# USB_OTG_FS.net
KiCad netlist of a schematic drawn in Altium Designer
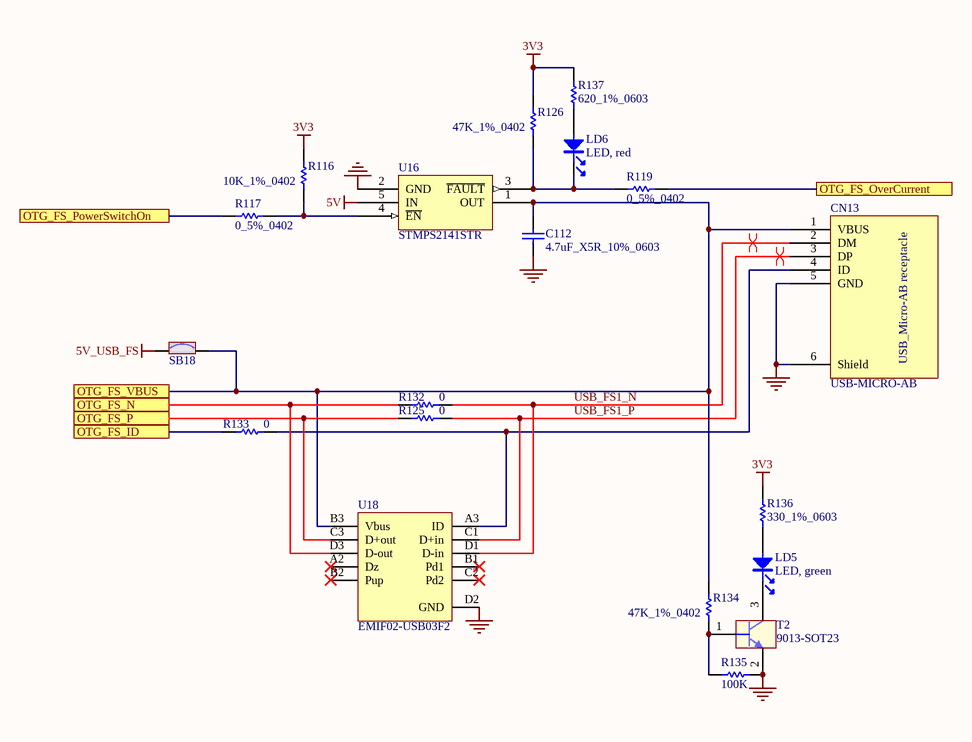
[diagram p0: USB_OTG_FS.SchDoc]

(export (version "E")
  (design (tool "Eeschema 10.0.6"))
  (components
    (comp (ref "C112")
      (value "4.7uF_X5R_10%_0603")
      (footprint "0603C")
      (description "Capacitor,4.7uF,16V, X5R,10%,0603,YAGEO")
      (libsource (lib "MCD_TOOLS") (part "Cap_4.7uF_X5R_10%_0603"))
    )
    (comp (ref "CN13")
      (value "USB-MICRO-AB")
      (footprint "USB-MICRO-AB")
      (description "USB-MICRO-AB, 47590-0001, SMT, MOLEX")
      (libsource (lib "MCD_TOOLS") (part "USB-MICRO-AB"))
    )
    (comp (ref "LD5")
      (value "LED, green")
      (footprint "0603D")
      (description "LED, green, 0603")
      (libsource (lib "MCD_TOOLS") (part "LED_green"))
    )
    (comp (ref "LD6")
      (value "LED, red")
      (footprint "0603D")
      (description "LED, red, 0603")
      (libsource (lib "MCD_TOOLS") (part "LED_red"))
    )
    (comp (ref "R116")
      (value "10K_1%_0402")
      (footprint "0402R")
      (description "Resistor,10K,0402,1%,YAGEO")
      (libsource (lib "MCD_TOOLS") (part "Res_10K_1%_0402"))
    )
    (comp (ref "R117")
      (value "0_5%_0402")
      (footprint "0402R")
      (description "Resistor,0,0402,5%,YAGEO")
      (libsource (lib "MCD_TOOLS") (part "Res_0_5%_0402"))
    )
    (comp (ref "R119")
      (value "0_5%_0402")
      (footprint "0402R")
      (description "Resistor,0,0402,5%,YAGEO")
      (libsource (lib "MCD_TOOLS") (part "Res_0_5%_0402"))
    )
    (comp (ref "R125")
      (value "0")
      (footprint "0402R")
      (description "Resistor,0,0402,5%,YAGEO")
      (libsource (lib "MCD_TOOLS") (part "Res_0_5%_0402"))
    )
    (comp (ref "R126")
      (value "47K_1%_0402")
      (footprint "0402R")
      (description "Resistor,47K,0402,1%,YAGEO")
      (libsource (lib "MCD_TOOLS") (part "Res_47K_1%_0402"))
    )
    (comp (ref "R132")
      (value "0")
      (footprint "0402R")
      (description "Resistor,0,0402,5%,YAGEO")
      (libsource (lib "MCD_TOOLS") (part "Res_0_5%_0402"))
    )
    (comp (ref "R133")
      (value "0")
      (footprint "0402R")
      (description "Resistor,0,0402,5%,YAGEO")
      (libsource (lib "MCD_TOOLS") (part "Res_0_5%_0402"))
    )
    (comp (ref "R134")
      (value "47K_1%_0402")
      (footprint "0402R")
      (description "Resistor,47K,0402,1%,YAGEO")
      (libsource (lib "MCD_TOOLS") (part "Res_47K_1%_0402"))
    )
    (comp (ref "R135")
      (value "100K")
      (footprint "0402R")
      (description "Resistor,100K,0402,1%,YAGEO")
      (libsource (lib "MCD_TOOLS") (part "Res_100K_1%_0402"))
    )
    (comp (ref "R136")
      (value "330_1%_0603")
      (footprint "0603R")
      (description "Resistor,330,0603,1%,YAGEO")
      (libsource (lib "MCD_TOOLS") (part "Res_330_1%_0603"))
    )
    (comp (ref "R137")
      (value "620_1%_0603")
      (footprint "0603R")
      (description "Resistor,620,0603,1%,VISHAY")
      (libsource (lib "MCD_TOOLS") (part "Res_620_1%_0603"))
    )
    (comp (ref "SB18")
      (value "Solder Bridge ON")
      (footprint "JP2_SMD")
      (libsource (lib "MCD_TOOLS") (part "SB_ON"))
    )
    (comp (ref "T2")
      (value "9013-SOT23")
      (footprint "SOT23")
      (description "NPN Bipolar Transistor")
      (libsource (lib "MCD_TOOLS") (part "9013-SOT23"))
    )
    (comp (ref "U16")
      (value "STMPS2141STR")
      (footprint "SOT23-5L")
      (description "Enhanced single channel power switches")
      (libsource (lib "MCD_TOOLS") (part "STMPS2141STR"))
    )
    (comp (ref "U18")
      (value "EMIF02-USB03F2")
      (footprint "Flip Chip")
      (description "2-line IPAD, EMI filter including ESD protection")
      (libsource (lib "MCD_TOOLS") (part "EMIF02-USB03F2"))
    )
  )
  (nets
    (net (code "1") (name "/OTG_FS_ID") (class "Default")
      (node (ref "R133") (pin "1") (pinfunction "1_1") (pintype "passive"))
    )
    (net (code "2") (name "/OTG_FS_N") (class "Default")
      (node (ref "R132") (pin "1") (pinfunction "1_1") (pintype "passive"))
      (node (ref "U18") (pin "D3") (pinfunction "D-out_D3") (pintype "passive"))
    )
    (net (code "3") (name "/OTG_FS_OverCurrent") (class "Default")
      (node (ref "R119") (pin "2") (pinfunction "2_2") (pintype "passive"))
    )
    (net (code "4") (name "/OTG_FS_P") (class "Default")
      (node (ref "R125") (pin "1") (pinfunction "1_1") (pintype "passive"))
      (node (ref "U18") (pin "C3") (pinfunction "D+out_C3") (pintype "passive"))
    )
    (net (code "5") (name "/OTG_FS_PowerSwitchOn") (class "Default")
      (node (ref "R117") (pin "1") (pinfunction "1_1") (pintype "passive"))
    )
    (net (code "6") (name "/OTG_FS_VBUS") (class "Default")
      (node (ref "C112") (pin "2") (pinfunction "2_2") (pintype "passive"))
      (node (ref "CN13") (pin "1") (pinfunction "VBUS_1") (pintype "passive"))
      (node (ref "R134") (pin "2") (pinfunction "2_2") (pintype "passive"))
      (node (ref "SB18") (pin "2") (pinfunction "2_2") (pintype "passive"))
      (node (ref "U16") (pin "1") (pinfunction "OUT_1") (pintype "passive"))
      (node (ref "U18") (pin "B3") (pinfunction "Vbus_B3") (pintype "passive"))
    )
    (net (code "7") (name "/USB_FS1_N") (class "Default")
      (node (ref "CN13") (pin "2") (pinfunction "DM_2") (pintype "passive"))
      (node (ref "R132") (pin "2") (pinfunction "2_2") (pintype "passive"))
      (node (ref "U18") (pin "D1") (pinfunction "D-in_D1") (pintype "passive"))
    )
    (net (code "8") (name "/USB_FS1_P") (class "Default")
      (node (ref "CN13") (pin "3") (pinfunction "DP_3") (pintype "passive"))
      (node (ref "R125") (pin "2") (pinfunction "2_2") (pintype "passive"))
      (node (ref "U18") (pin "C1") (pinfunction "D+in_C1") (pintype "passive"))
    )
    (net (code "9") (name "3V3") (class "Default")
      (node (ref "R116") (pin "2") (pinfunction "2_2") (pintype "passive"))
      (node (ref "R126") (pin "2") (pinfunction "2_2") (pintype "passive"))
      (node (ref "R136") (pin "2") (pinfunction "2_2") (pintype "passive"))
      (node (ref "R137") (pin "2") (pinfunction "2_2") (pintype "passive"))
    )
    (net (code "10") (name "5V") (class "Default")
      (node (ref "U16") (pin "5") (pinfunction "IN_5") (pintype "passive"))
    )
    (net (code "11") (name "5V_USB_FS") (class "Default")
      (node (ref "SB18") (pin "1") (pinfunction "1_1") (pintype "passive"))
    )
    (net (code "12") (name "GND") (class "Default")
      (node (ref "C112") (pin "1") (pinfunction "1_1") (pintype "passive"))
      (node (ref "CN13") (pin "5") (pinfunction "GND_5") (pintype "passive"))
      (node (ref "CN13") (pin "6") (pinfunction "Shield_6") (pintype "passive"))
      (node (ref "R135") (pin "2") (pinfunction "2_2") (pintype "passive"))
      (node (ref "T2") (pin "2") (pinfunction "E_2") (pintype "passive"))
      (node (ref "U16") (pin "2") (pinfunction "GND_2") (pintype "passive"))
      (node (ref "U18") (pin "D2") (pinfunction "GND_D2") (pintype "passive"))
    )
    (net (code "13") (name "Net-(CN13-ID)") (class "Default")
      (node (ref "CN13") (pin "4") (pinfunction "ID_4") (pintype "passive"))
      (node (ref "R133") (pin "2") (pinfunction "2_2") (pintype "passive"))
      (node (ref "U18") (pin "A3") (pinfunction "ID_A3") (pintype "passive"))
    )
    (net (code "14") (name "Net-(LD5-Pad1)") (class "Default")
      (node (ref "LD5") (pin "1") (pintype "passive"))
      (node (ref "R136") (pin "1") (pinfunction "1_1") (pintype "passive"))
    )
    (net (code "15") (name "Net-(LD6-Pad1)") (class "Default")
      (node (ref "LD6") (pin "1") (pintype "passive"))
      (node (ref "R137") (pin "1") (pinfunction "1_1") (pintype "passive"))
    )
    (net (code "16") (name "Net-(T2-B)") (class "Default")
      (node (ref "R134") (pin "1") (pinfunction "1_1") (pintype "passive"))
      (node (ref "R135") (pin "1") (pinfunction "1_1") (pintype "passive"))
      (node (ref "T2") (pin "1") (pinfunction "B_1") (pintype "passive"))
    )
    (net (code "17") (name "Net-(T2-C)") (class "Default")
      (node (ref "LD5") (pin "2") (pintype "passive"))
      (node (ref "T2") (pin "3") (pinfunction "C_3") (pintype "passive"))
    )
    (net (code "18") (name "Net-(U16-~{EN})") (class "Default")
      (node (ref "R116") (pin "1") (pinfunction "1_1") (pintype "passive"))
      (node (ref "R117") (pin "2") (pinfunction "2_2") (pintype "passive"))
      (node (ref "U16") (pin "4") (pinfunction "~{EN}_4") (pintype "input"))
    )
    (net (code "19") (name "Net-(U16-~{FAULT})") (class "Default")
      (node (ref "LD6") (pin "2") (pintype "passive"))
      (node (ref "R119") (pin "1") (pinfunction "1_1") (pintype "passive"))
      (node (ref "R126") (pin "1") (pinfunction "1_1") (pintype "passive"))
      (node (ref "U16") (pin "3") (pinfunction "~{FAULT}_3") (pintype "output"))
    )
    (net (code "20") (name "unconnected-(U18-Dz-PadA2)") (class "Default")
      (node (ref "U18") (pin "A2") (pinfunction "Dz_A2") (pintype "passive+no_connect"))
    )
    (net (code "21") (name "unconnected-(U18-Pd1-PadB1)") (class "Default")
      (node (ref "U18") (pin "B1") (pinfunction "Pd1_B1") (pintype "passive+no_connect"))
    )
    (net (code "22") (name "unconnected-(U18-Pd2-PadC2)") (class "Default")
      (node (ref "U18") (pin "C2") (pinfunction "Pd2_C2") (pintype "passive+no_connect"))
    )
    (net (code "23") (name "unconnected-(U18-Pup-PadB2)") (class "Default")
      (node (ref "U18") (pin "B2") (pinfunction "Pup_B2") (pintype "passive+no_connect"))
    )
  )
)
